# Sheet1.net
KiCad netlist of a schematic drawn in Altium Designer
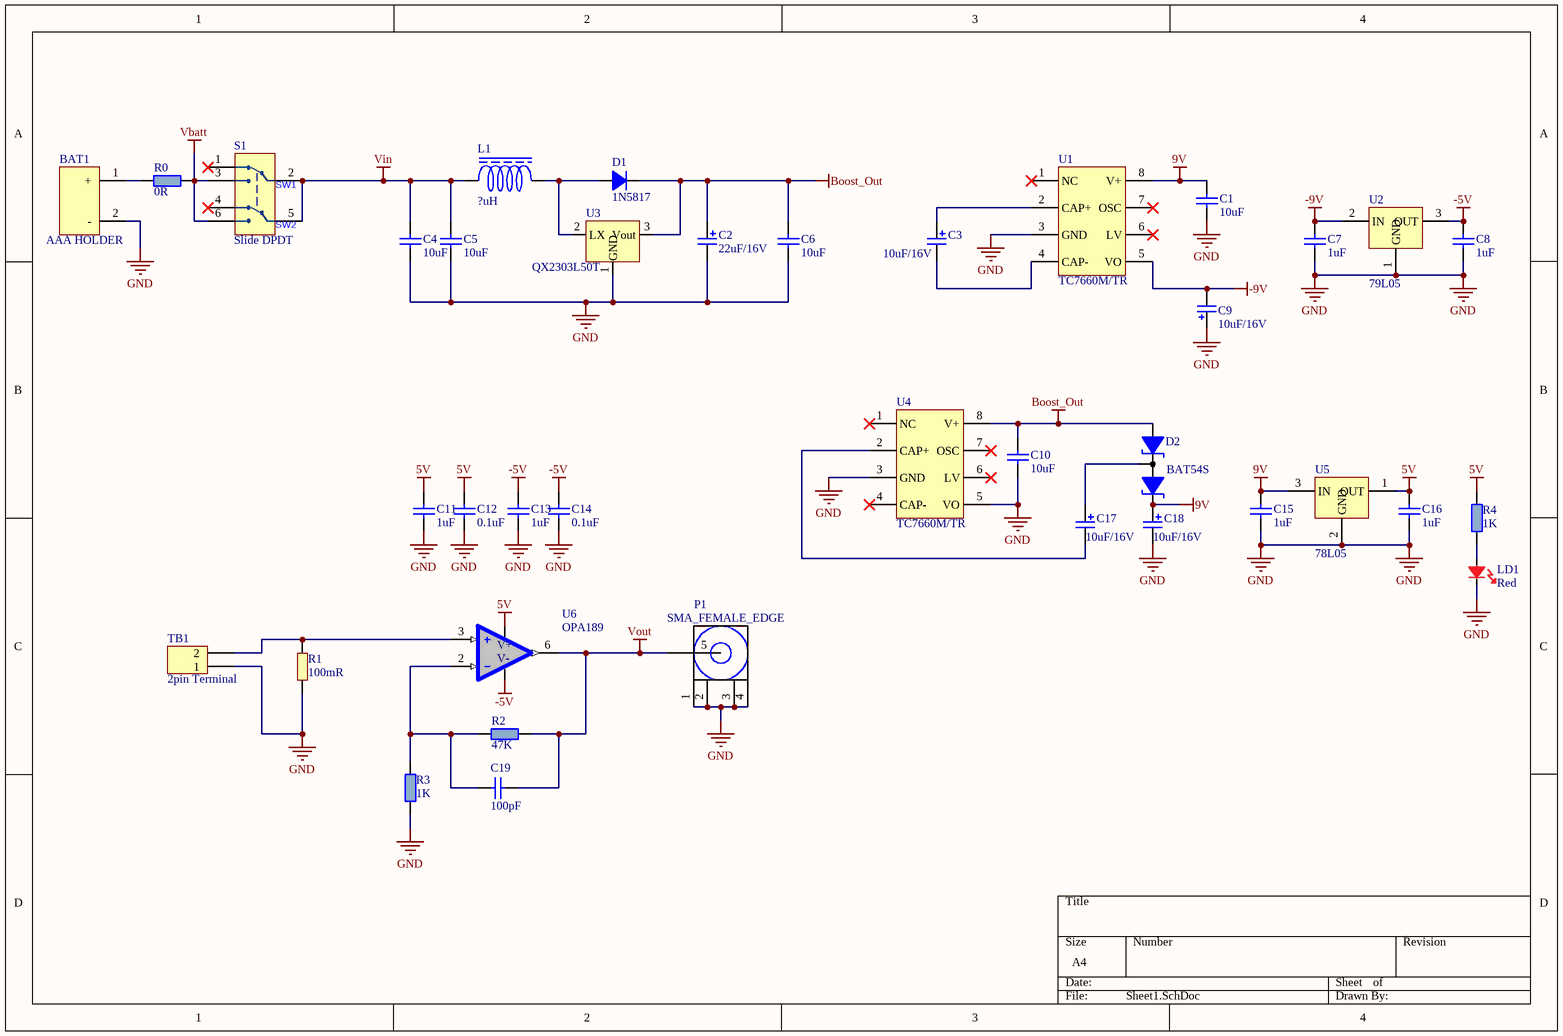
[diagram p0: Sheet1.SchDoc]

(export (version "E")
  (design (tool "Eeschema 10.0.6"))
  (components
    (comp (ref "BAT1")
      (value "AAA HOLDER")
      (footprint "AAA Battery Holder")
      (libsource (lib "BC_Schematic Lib") (part "BATT_HOLDER_AAA"))
    )
    (comp (ref "C1")
      (value "10uF")
      (footprint "0805_CAP")
      (description "Capacitor, Ceramic,, ?F, ?V, 0805")
      (fields
        (field (name "MANUFACTURER") "Murata")
        (field (name "ENGINEER’S NAME") "WZ")
        (field (name "VERIFIED") "Correct desc from 50v to 16v")
      )
      (libsource (lib "BC_Schematic Lib SMT") (part "CC_?F_0805"))
    )
    (comp (ref "C2")
      (value "22uF/16V")
      (footprint "CASEB_EIA3528-21")
      (libsource (lib "BC_Schematic Lib SMT") (part "CT_22uF_16V_3528"))
    )
    (comp (ref "C3")
      (value "10uF/16V")
      (footprint "CASEA_EIA3216-18")
      (libsource (lib "BC_Schematic Lib SMT") (part "CT_10uF_16V_3216"))
    )
    (comp (ref "C4")
      (value "10uF")
      (footprint "0805_CAP")
      (description "Capacitor, Ceramic,, ?F, ?V, 0805")
      (fields
        (field (name "MANUFACTURER") "Murata")
        (field (name "ENGINEER’S NAME") "WZ")
        (field (name "VERIFIED") "Correct desc from 50v to 16v")
      )
      (libsource (lib "BC_Schematic Lib SMT") (part "CC_?F_0805"))
    )
    (comp (ref "C5")
      (value "10uF")
      (footprint "0805_CAP")
      (description "Capacitor, Ceramic,, ?F, ?V, 0805")
      (fields
        (field (name "MANUFACTURER") "Murata")
        (field (name "ENGINEER’S NAME") "WZ")
        (field (name "VERIFIED") "Correct desc from 50v to 16v")
      )
      (libsource (lib "BC_Schematic Lib SMT") (part "CC_?F_0805"))
    )
    (comp (ref "C6")
      (value "10uF")
      (footprint "0805_CAP")
      (description "Capacitor, Ceramic,, ?F, ?V, 0805")
      (fields
        (field (name "MANUFACTURER") "Murata")
        (field (name "ENGINEER’S NAME") "WZ")
        (field (name "VERIFIED") "Correct desc from 50v to 16v")
      )
      (libsource (lib "BC_Schematic Lib SMT") (part "CC_?F_0805"))
    )
    (comp (ref "C7")
      (value "1uF")
      (footprint "0805_CAP")
      (description "Capacitor, Ceramic,, ?F, ?V, 0805")
      (fields
        (field (name "MANUFACTURER") "Murata")
        (field (name "ENGINEER’S NAME") "WZ")
        (field (name "VERIFIED") "Correct desc from 50v to 16v")
      )
      (libsource (lib "BC_Schematic Lib SMT") (part "CC_?F_0805"))
    )
    (comp (ref "C8")
      (value "1uF")
      (footprint "0805_CAP")
      (description "Capacitor, Ceramic,, ?F, ?V, 0805")
      (fields
        (field (name "MANUFACTURER") "Murata")
        (field (name "ENGINEER’S NAME") "WZ")
        (field (name "VERIFIED") "Correct desc from 50v to 16v")
      )
      (libsource (lib "BC_Schematic Lib SMT") (part "CC_?F_0805"))
    )
    (comp (ref "C9")
      (value "10uF/16V")
      (footprint "CASEA_EIA3216-18")
      (libsource (lib "BC_Schematic Lib SMT") (part "CT_10uF_16V_3216"))
    )
    (comp (ref "C10")
      (value "10uF")
      (footprint "0805_CAP")
      (description "Capacitor, Ceramic,, ?F, ?V, 0805")
      (fields
        (field (name "MANUFACTURER") "Murata")
        (field (name "ENGINEER’S NAME") "WZ")
        (field (name "VERIFIED") "Correct desc from 50v to 16v")
      )
      (libsource (lib "BC_Schematic Lib SMT") (part "CC_?F_0805"))
    )
    (comp (ref "C11")
      (value "1uF")
      (footprint "0805_CAP")
      (description "Capacitor, Ceramic,, ?F, ?V, 0805")
      (fields
        (field (name "MANUFACTURER") "Murata")
        (field (name "ENGINEER’S NAME") "WZ")
        (field (name "VERIFIED") "Correct desc from 50v to 16v")
      )
      (libsource (lib "BC_Schematic Lib SMT") (part "CC_?F_0805"))
    )
    (comp (ref "C12")
      (value "0.1uF")
      (footprint "0805_CAP")
      (description "Capacitor, Ceramic,, ?F, ?V, 0805")
      (fields
        (field (name "MANUFACTURER") "Murata")
        (field (name "ENGINEER’S NAME") "WZ")
        (field (name "VERIFIED") "Correct desc from 50v to 16v")
      )
      (libsource (lib "BC_Schematic Lib SMT") (part "CC_?F_0805"))
    )
    (comp (ref "C13")
      (value "1uF")
      (footprint "0805_CAP")
      (description "Capacitor, Ceramic,, ?F, ?V, 0805")
      (fields
        (field (name "MANUFACTURER") "Murata")
        (field (name "ENGINEER’S NAME") "WZ")
        (field (name "VERIFIED") "Correct desc from 50v to 16v")
      )
      (libsource (lib "BC_Schematic Lib SMT") (part "CC_?F_0805"))
    )
    (comp (ref "C14")
      (value "0.1uF")
      (footprint "0805_CAP")
      (description "Capacitor, Ceramic,, ?F, ?V, 0805")
      (fields
        (field (name "MANUFACTURER") "Murata")
        (field (name "ENGINEER’S NAME") "WZ")
        (field (name "VERIFIED") "Correct desc from 50v to 16v")
      )
      (libsource (lib "BC_Schematic Lib SMT") (part "CC_?F_0805"))
    )
    (comp (ref "C15")
      (value "1uF")
      (footprint "0805_CAP")
      (description "Capacitor, Ceramic,, ?F, ?V, 0805")
      (fields
        (field (name "MANUFACTURER") "Murata")
        (field (name "ENGINEER’S NAME") "WZ")
        (field (name "VERIFIED") "Correct desc from 50v to 16v")
      )
      (libsource (lib "BC_Schematic Lib SMT") (part "CC_?F_0805"))
    )
    (comp (ref "C16")
      (value "1uF")
      (footprint "0805_CAP")
      (description "Capacitor, Ceramic,, ?F, ?V, 0805")
      (fields
        (field (name "MANUFACTURER") "Murata")
        (field (name "ENGINEER’S NAME") "WZ")
        (field (name "VERIFIED") "Correct desc from 50v to 16v")
      )
      (libsource (lib "BC_Schematic Lib SMT") (part "CC_?F_0805"))
    )
    (comp (ref "C17")
      (value "10uF/16V")
      (footprint "CASEA_EIA3216-18")
      (libsource (lib "BC_Schematic Lib SMT") (part "CT_10uF_16V_3216"))
    )
    (comp (ref "C18")
      (value "10uF/16V")
      (footprint "CASEA_EIA3216-18")
      (libsource (lib "BC_Schematic Lib SMT") (part "CT_10uF_16V_3216"))
    )
    (comp (ref "C19")
      (value "100pF")
      (footprint "0805_CAP")
      (description "Capacitor, Ceramic,, ?F, ?V, 0805")
      (fields
        (field (name "MANUFACTURER") "Murata")
        (field (name "ENGINEER’S NAME") "WZ")
        (field (name "VERIFIED") "Correct desc from 50v to 16v")
      )
      (libsource (lib "BC_Schematic Lib SMT") (part "CC_?F_0805"))
    )
    (comp (ref "D1")
      (value "1N5817")
      (footprint "SOD123")
      (libsource (lib "BC_Schematic Lib SMT") (part "DI_1N5817"))
    )
    (comp (ref "D2")
      (value "BAT54S")
      (footprint "SOT23")
      (libsource (lib "BC_Schematic Lib SMT") (part "DI_BAT54S"))
    )
    (comp (ref "L1")
      (value "?uH")
      (footprint "IND_40x45x3.2")
      (libsource (lib "BC_Schematic Lib SMT") (part "IND_?uH_4045"))
    )
    (comp (ref "LD1")
      (value "Red")
      (footprint "LED0805_Red")
      (description "LED, Red, 2.0V, Imax 30mA, 120deg. At 20mA => Wavelength = 630nm, 230mcd, 0805")
      (fields (field (name "MANUFACTURER") "Kingbright"))
      (libsource (lib "BC_Schematic Lib SMT") (part "LED_RED230mcd_2013"))
    )
    (comp (ref "P1")
      (value "SMA_FEMALE_EDGE")
      (footprint "SMA_EDGE_CONNECTOR")
      (description "SMA FEMALE Edge Connector")
      (libsource (lib "BC_Schematic Lib SMT") (part "CONN_SMA_RF_EDGE"))
    )
    (comp (ref "R0")
      (value "0R")
      (footprint "0805_res")
      (description "Resistor, ?ohm, 0805")
      (fields (field (name "MANUFACTURER") "MULTICOMP"))
      (libsource (lib "") (part "RS_?R_0805_2"))
    )
    (comp (ref "R1")
      (value "100mR")
      (footprint "2512-1.8")
      (description "2512 Resistor")
      (libsource (lib "BC_Schematic Lib SMT") (part "RS_?R_2512"))
    )
    (comp (ref "R2")
      (value "47K")
      (footprint "0805_res")
      (description "Resistor, ?ohm, 0805")
      (fields (field (name "MANUFACTURER") "MULTICOMP"))
      (libsource (lib "") (part "RS_?R_0805_1"))
    )
    (comp (ref "R3")
      (value "1K")
      (footprint "0805_res")
      (description "Resistor, ?ohm, 0805")
      (fields (field (name "MANUFACTURER") "MULTICOMP"))
      (libsource (lib "BC_Schematic Lib SMT") (part "RS_?R_0805"))
    )
    (comp (ref "R4")
      (value "1K")
      (footprint "0805_res")
      (description "Resistor, ?ohm, 0805")
      (fields (field (name "MANUFACTURER") "MULTICOMP"))
      (libsource (lib "BC_Schematic Lib SMT") (part "RS_?R_0805"))
    )
    (comp (ref "S1")
      (value "Slide DPDT")
      (footprint "SW_DPDT_SMD")
      (libsource (lib "BC_Schematic Lib SMT") (part "SW_Slide_DPDT"))
    )
    (comp (ref "TB1")
      (value "2pin Terminal")
      (footprint "TB_SCW_5mm_2way_Horz_TE101")
      (description "Screw Terminal Block 5mm Pitch 2 Position, Green")
      (fields (field (name "MANUFACTURER") "Dinkle"))
      (libsource (lib "BC_Schematic Lib") (part "TE101_2W_5mm"))
    )
    (comp (ref "U1")
      (value "TC7660M/TR")
      (footprint "SO8")
      (description "LCSC#: C512761\r\nMfr.#: TC7660M/TR\r\nMfr: HGSEMI\r\nSOP-8 Charge Pump")
      (libsource (lib "BC_Schematic Lib SMT") (part "IC_TC7660M/TR"))
    )
    (comp (ref "U2")
      (value "79L05")
      (footprint "SOT89")
      (libsource (lib "BC_Schematic Lib SMT") (part "LDO_79L05"))
    )
    (comp (ref "U3")
      (value "QX2303L50T")
      (footprint "SOT23")
      (libsource (lib "BC_Schematic Lib SMT") (part "IC_PMIC_SW_QX2303L50T"))
    )
    (comp (ref "U4")
      (value "TC7660M/TR")
      (footprint "SO8")
      (description "LCSC#: C512761\r\nMfr.#: TC7660M/TR\r\nMfr: HGSEMI\r\nSOP-8 Charge Pump")
      (libsource (lib "BC_Schematic Lib SMT") (part "IC_TC7660M/TR"))
    )
    (comp (ref "U5")
      (value "78L05")
      (footprint "SOT89")
      (libsource (lib "BC_Schematic Lib SMT") (part "LDO_78L05"))
    )
    (comp (ref "U6")
      (value "OPA189")
      (footprint "SO8")
      (libsource (lib "BC_Schematic Lib SMT") (part "IC_OP_OPA189IDR"))
    )
  )
  (nets
    (net (code "1") (name "-5V") (class "Default")
      (node (ref "C13") (pin "2") (pinfunction "2_2") (pintype "passive"))
      (node (ref "C14") (pin "2") (pinfunction "2_2") (pintype "passive"))
      (node (ref "C8") (pin "2") (pinfunction "2_2") (pintype "passive"))
      (node (ref "U2") (pin "3") (pinfunction "OUT_3") (pintype "passive"))
      (node (ref "U6") (pin "4") (pinfunction "V-_4") (pintype "power_in"))
    )
    (net (code "2") (name "-9V") (class "Default")
      (node (ref "C7") (pin "2") (pinfunction "2_2") (pintype "passive"))
      (node (ref "C9") (pin "2") (pinfunction "K_2") (pintype "passive"))
      (node (ref "U1") (pin "5") (pinfunction "VO_5") (pintype "passive"))
      (node (ref "U2") (pin "2") (pinfunction "IN_2") (pintype "passive"))
    )
    (net (code "3") (name "5V") (class "Default")
      (node (ref "C11") (pin "2") (pinfunction "2_2") (pintype "passive"))
      (node (ref "C12") (pin "2") (pinfunction "2_2") (pintype "passive"))
      (node (ref "C16") (pin "2") (pinfunction "2_2") (pintype "passive"))
      (node (ref "R4") (pin "2") (pinfunction "2_2") (pintype "passive"))
      (node (ref "U5") (pin "1") (pinfunction "OUT_1") (pintype "passive"))
      (node (ref "U6") (pin "7") (pinfunction "V+_7") (pintype "power_in"))
    )
    (net (code "4") (name "9V") (class "Default")
      (node (ref "C1") (pin "2") (pinfunction "2_2") (pintype "passive"))
      (node (ref "C15") (pin "2") (pinfunction "2_2") (pintype "passive"))
      (node (ref "C18") (pin "1") (pinfunction "A_1") (pintype "passive"))
      (node (ref "D2") (pin "2") (pinfunction "K2_2") (pintype "passive"))
      (node (ref "U1") (pin "8") (pinfunction "V+_8") (pintype "power_in"))
      (node (ref "U5") (pin "3") (pinfunction "IN_3") (pintype "passive"))
    )
    (net (code "5") (name "Boost_Out") (class "Default")
      (node (ref "C10") (pin "2") (pinfunction "2_2") (pintype "passive"))
      (node (ref "C2") (pin "1") (pinfunction "A_1") (pintype "passive"))
      (node (ref "C6") (pin "2") (pinfunction "2_2") (pintype "passive"))
      (node (ref "D1") (pin "2") (pinfunction "K_2") (pintype "passive"))
      (node (ref "D2") (pin "1") (pinfunction "A1_1") (pintype "passive"))
      (node (ref "U3") (pin "3") (pinfunction "Vout_3") (pintype "power_in"))
      (node (ref "U4") (pin "8") (pinfunction "V+_8") (pintype "power_in"))
    )
    (net (code "6") (name "GND") (class "Default")
      (node (ref "BAT1") (pin "2") (pinfunction "-_2") (pintype "passive"))
      (node (ref "C1") (pin "1") (pinfunction "1_1") (pintype "passive"))
      (node (ref "C10") (pin "1") (pinfunction "1_1") (pintype "passive"))
      (node (ref "C11") (pin "1") (pinfunction "1_1") (pintype "passive"))
      (node (ref "C12") (pin "1") (pinfunction "1_1") (pintype "passive"))
      (node (ref "C13") (pin "1") (pinfunction "1_1") (pintype "passive"))
      (node (ref "C14") (pin "1") (pinfunction "1_1") (pintype "passive"))
      (node (ref "C15") (pin "1") (pinfunction "1_1") (pintype "passive"))
      (node (ref "C16") (pin "1") (pinfunction "1_1") (pintype "passive"))
      (node (ref "C18") (pin "2") (pinfunction "K_2") (pintype "passive"))
      (node (ref "C2") (pin "2") (pinfunction "K_2") (pintype "passive"))
      (node (ref "C4") (pin "1") (pinfunction "1_1") (pintype "passive"))
      (node (ref "C5") (pin "1") (pinfunction "1_1") (pintype "passive"))
      (node (ref "C6") (pin "1") (pinfunction "1_1") (pintype "passive"))
      (node (ref "C7") (pin "1") (pinfunction "1_1") (pintype "passive"))
      (node (ref "C8") (pin "1") (pinfunction "1_1") (pintype "passive"))
      (node (ref "C9") (pin "1") (pinfunction "A_1") (pintype "passive"))
      (node (ref "LD1") (pin "2") (pinfunction "K_2") (pintype "passive"))
      (node (ref "P1") (pin "1") (pinfunction "1_1") (pintype "passive"))
      (node (ref "P1") (pin "2") (pinfunction "2_2") (pintype "passive"))
      (node (ref "P1") (pin "3") (pinfunction "3_3") (pintype "passive"))
      (node (ref "P1") (pin "4") (pinfunction "4_4") (pintype "passive"))
      (node (ref "R1") (pin "1") (pinfunction "1_1") (pintype "passive"))
      (node (ref "R3") (pin "1") (pinfunction "1_1") (pintype "passive"))
      (node (ref "TB1") (pin "1") (pinfunction "1_1") (pintype "passive"))
      (node (ref "U1") (pin "3") (pinfunction "GND_3") (pintype "power_in"))
      (node (ref "U2") (pin "1") (pinfunction "GND_1") (pintype "passive"))
      (node (ref "U3") (pin "1") (pinfunction "GND_1") (pintype "power_in"))
      (node (ref "U4") (pin "3") (pinfunction "GND_3") (pintype "power_in"))
      (node (ref "U4") (pin "5") (pinfunction "VO_5") (pintype "passive"))
      (node (ref "U5") (pin "2") (pinfunction "GND_2") (pintype "passive"))
    )
    (net (code "7") (name "Net-(BAT1-+)") (class "Default")
      (node (ref "BAT1") (pin "1") (pinfunction "+_1") (pintype "passive"))
      (node (ref "R0") (pin "2") (pinfunction "2_2") (pintype "passive"))
    )
    (net (code "8") (name "Net-(C3-A)") (class "Default")
      (node (ref "C3") (pin "1") (pinfunction "A_1") (pintype "passive"))
      (node (ref "U1") (pin "2") (pinfunction "CAP+_2") (pintype "passive"))
    )
    (net (code "9") (name "Net-(C3-K)") (class "Default")
      (node (ref "C3") (pin "2") (pinfunction "K_2") (pintype "passive"))
      (node (ref "U1") (pin "4") (pinfunction "CAP-_4") (pintype "passive"))
    )
    (net (code "10") (name "Net-(C17-A)") (class "Default")
      (node (ref "C17") (pin "1") (pinfunction "A_1") (pintype "passive"))
      (node (ref "D2") (pin "3") (pinfunction "S_3") (pintype "passive"))
    )
    (net (code "11") (name "Net-(C17-K)") (class "Default")
      (node (ref "C17") (pin "2") (pinfunction "K_2") (pintype "passive"))
      (node (ref "U4") (pin "2") (pinfunction "CAP+_2") (pintype "passive"))
    )
    (net (code "12") (name "Net-(D1-A)") (class "Default")
      (node (ref "D1") (pin "1") (pinfunction "A_1") (pintype "passive"))
      (node (ref "L1") (pin "2") (pinfunction "2_2") (pintype "passive"))
      (node (ref "U3") (pin "2") (pinfunction "LX_2") (pintype "power_in"))
    )
    (net (code "13") (name "Net-(LD1-A)") (class "Default")
      (node (ref "LD1") (pin "1") (pinfunction "A_1") (pintype "passive"))
      (node (ref "R4") (pin "1") (pinfunction "1_1") (pintype "passive"))
    )
    (net (code "14") (name "Net-(U6A-IN+)") (class "Default")
      (node (ref "R1") (pin "2") (pinfunction "2_2") (pintype "passive"))
      (node (ref "TB1") (pin "2") (pinfunction "2_2") (pintype "passive"))
      (node (ref "U6") (pin "3") (pinfunction "IN+_3") (pintype "input"))
    )
    (net (code "15") (name "Net-(U6A-IN-)") (class "Default")
      (node (ref "C19") (pin "2") (pinfunction "2_2") (pintype "passive"))
      (node (ref "R2") (pin "1") (pinfunction "1_1") (pintype "passive"))
      (node (ref "R3") (pin "2") (pinfunction "2_2") (pintype "passive"))
      (node (ref "U6") (pin "2") (pinfunction "IN-_2") (pintype "input"))
    )
    (net (code "16") (name "Vbatt") (class "Default")
      (node (ref "R0") (pin "1") (pinfunction "1_1") (pintype "passive"))
      (node (ref "S1") (pin "3") (pinfunction "NO1_3") (pintype "passive"))
      (node (ref "S1") (pin "6") (pinfunction "NO2_6") (pintype "passive"))
    )
    (net (code "17") (name "Vin") (class "Default")
      (node (ref "C4") (pin "2") (pinfunction "2_2") (pintype "passive"))
      (node (ref "C5") (pin "2") (pinfunction "2_2") (pintype "passive"))
      (node (ref "L1") (pin "1") (pinfunction "1_1") (pintype "passive"))
      (node (ref "S1") (pin "2") (pinfunction "C1_2") (pintype "passive"))
      (node (ref "S1") (pin "5") (pinfunction "C2_5") (pintype "passive"))
    )
    (net (code "18") (name "Vout") (class "Default")
      (node (ref "C19") (pin "1") (pinfunction "1_1") (pintype "passive"))
      (node (ref "P1") (pin "5") (pinfunction "5_5") (pintype "passive"))
      (node (ref "R2") (pin "2") (pinfunction "2_2") (pintype "passive"))
      (node (ref "U6") (pin "6") (pinfunction "OUT_6") (pintype "output"))
    )
    (net (code "19") (name "unconnected-(S1-NC1-Pad1)") (class "Default")
      (node (ref "S1") (pin "1") (pinfunction "NC1_1") (pintype "passive+no_connect"))
    )
    (net (code "20") (name "unconnected-(S1-NC2-Pad4)") (class "Default")
      (node (ref "S1") (pin "4") (pinfunction "NC2_4") (pintype "passive+no_connect"))
    )
    (net (code "21") (name "unconnected-(U1-LV-Pad6)") (class "Default")
      (node (ref "U1") (pin "6") (pinfunction "LV_6") (pintype "passive+no_connect"))
    )
    (net (code "22") (name "unconnected-(U1-NC-Pad1)") (class "Default")
      (node (ref "U1") (pin "1") (pinfunction "NC_1") (pintype "passive+no_connect"))
    )
    (net (code "23") (name "unconnected-(U1-OSC-Pad7)") (class "Default")
      (node (ref "U1") (pin "7") (pinfunction "OSC_7") (pintype "passive+no_connect"))
    )
    (net (code "24") (name "unconnected-(U4-CAP--Pad4)") (class "Default")
      (node (ref "U4") (pin "4") (pinfunction "CAP-_4") (pintype "passive+no_connect"))
    )
    (net (code "25") (name "unconnected-(U4-LV-Pad6)") (class "Default")
      (node (ref "U4") (pin "6") (pinfunction "LV_6") (pintype "passive+no_connect"))
    )
    (net (code "26") (name "unconnected-(U4-NC-Pad1)") (class "Default")
      (node (ref "U4") (pin "1") (pinfunction "NC_1") (pintype "passive+no_connect"))
    )
    (net (code "27") (name "unconnected-(U4-OSC-Pad7)") (class "Default")
      (node (ref "U4") (pin "7") (pinfunction "OSC_7") (pintype "passive+no_connect"))
    )
  )
)
